# Bus_Isolator.net
KiCad netlist of a schematic drawn in EAGLE
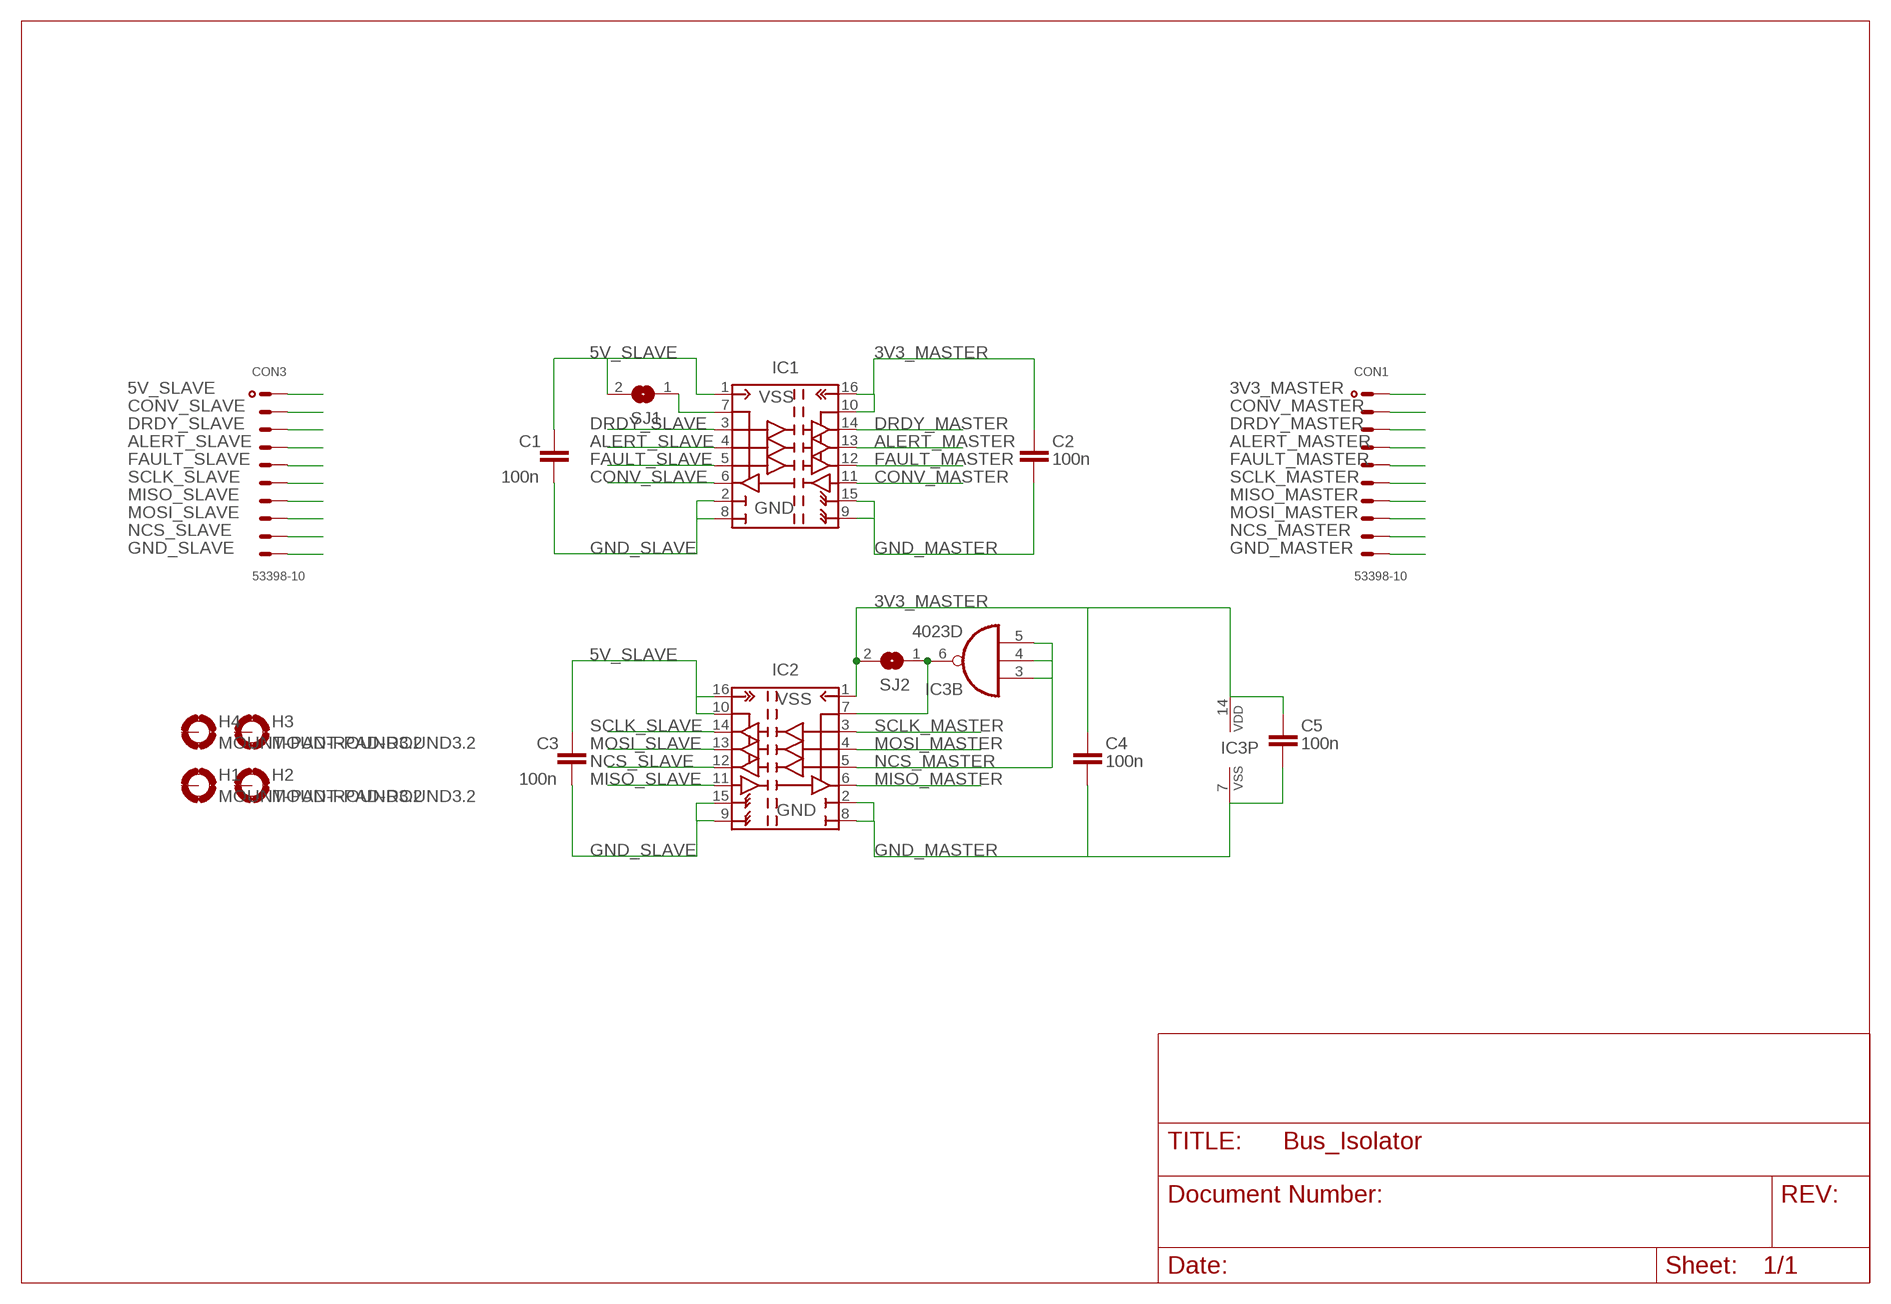
[diagram p0: schematic, sheet 1]

(export (version "E")
  (design (tool "Eeschema 10.0.6"))
  (components
    (comp (ref "C1")
      (value "100n")
      (footprint "eagle-import:C0805")
      (libsource (lib "eagle-import") (part "CSTD"))
    )
    (comp (ref "C2")
      (value "100n")
      (footprint "eagle-import:C0805")
      (libsource (lib "eagle-import") (part "CSTD"))
    )
    (comp (ref "C3")
      (value "100n")
      (footprint "eagle-import:C0805")
      (libsource (lib "eagle-import") (part "CSTD"))
    )
    (comp (ref "C4")
      (value "100n")
      (footprint "eagle-import:C0805")
      (libsource (lib "eagle-import") (part "CSTD"))
    )
    (comp (ref "C5")
      (value "100n")
      (footprint "eagle-import:C0805")
      (libsource (lib "eagle-import") (part "CSTD"))
    )
    (comp (ref "CON1")
      (value "53398-10")
      (footprint "eagle-import:53398-10")
      (libsource (lib "eagle-import") (part "53?-10398"))
    )
    (comp (ref "CON3")
      (value "53398-10")
      (footprint "eagle-import:53398-10")
      (libsource (lib "eagle-import") (part "53?-10398"))
    )
    (comp (ref "H1")
      (value "MOUNT-PAD-ROUND3.2")
      (footprint "eagle-import:3,2-PAD")
      (libsource (lib "eagle-import") (part "MOUNT-PAD-ROUND3.2"))
    )
    (comp (ref "H2")
      (value "MOUNT-PAD-ROUND3.2")
      (footprint "eagle-import:3,2-PAD")
      (libsource (lib "eagle-import") (part "MOUNT-PAD-ROUND3.2"))
    )
    (comp (ref "H3")
      (value "MOUNT-PAD-ROUND3.2")
      (footprint "eagle-import:3,2-PAD")
      (libsource (lib "eagle-import") (part "MOUNT-PAD-ROUND3.2"))
    )
    (comp (ref "H4")
      (value "MOUNT-PAD-ROUND3.2")
      (footprint "eagle-import:3,2-PAD")
      (libsource (lib "eagle-import") (part "MOUNT-PAD-ROUND3.2"))
    )
    (comp (ref "IC1")
      (value "ISO7241")
      (footprint "eagle-import:R-PDSO-G16")
      (libsource (lib "eagle-import") (part "ISO7241"))
    )
    (comp (ref "IC2")
      (value "ISO7241")
      (footprint "eagle-import:R-PDSO-G16")
      (libsource (lib "eagle-import") (part "ISO7241"))
    )
    (comp (ref "IC3")
      (value "4023D")
      (footprint "eagle-import:SO14")
      (libsource (lib "eagle-import") (part "4023D"))
    )
    (comp (ref "SJ1") (value "SJ") (footprint "eagle-import:SJ") (libsource (lib "eagle-import") (part "SJ")))
    (comp (ref "SJ2") (value "SJ") (footprint "eagle-import:SJ") (libsource (lib "eagle-import") (part "SJ")))
  )
  (nets
    (net (code "1") (name "/3V3_MASTER") (class "Default")
      (node (ref "C2") (pin "2") (pinfunction "2_2") (pintype "passive"))
      (node (ref "C4") (pin "2") (pinfunction "2_2") (pintype "passive"))
      (node (ref "C5") (pin "2") (pinfunction "2_2") (pintype "passive"))
      (node (ref "CON1") (pin "1") (pinfunction "1_1") (pintype "passive"))
      (node (ref "IC1") (pin "10") (pinfunction "EN2_10") (pintype "bidirectional"))
      (node (ref "IC1") (pin "16") (pinfunction "VCC2_16") (pintype "bidirectional"))
      (node (ref "IC2") (pin "1") (pinfunction "VCC1_1") (pintype "bidirectional"))
      (node (ref "IC3") (pin "14") (pinfunction "VDD_14") (pintype "power_in"))
      (node (ref "SJ2") (pin "2") (pinfunction "2_2") (pintype "passive"))
    )
    (net (code "2") (name "/5V_SLAVE") (class "Default")
      (node (ref "C1") (pin "2") (pinfunction "2_2") (pintype "passive"))
      (node (ref "C3") (pin "2") (pinfunction "2_2") (pintype "passive"))
      (node (ref "CON3") (pin "1") (pinfunction "1_1") (pintype "passive"))
      (node (ref "IC1") (pin "1") (pinfunction "VCC1_1") (pintype "bidirectional"))
      (node (ref "IC2") (pin "10") (pinfunction "EN2_10") (pintype "bidirectional"))
      (node (ref "IC2") (pin "16") (pinfunction "VCC2_16") (pintype "bidirectional"))
      (node (ref "SJ1") (pin "2") (pinfunction "2_2") (pintype "passive"))
    )
    (net (code "3") (name "/ALERT_MASTER") (class "Default")
      (node (ref "CON1") (pin "4") (pinfunction "4_4") (pintype "passive"))
      (node (ref "IC1") (pin "13") (pinfunction "OUT_B_13") (pintype "bidirectional"))
    )
    (net (code "4") (name "/ALERT_SLAVE") (class "Default")
      (node (ref "CON3") (pin "4") (pinfunction "4_4") (pintype "passive"))
      (node (ref "IC1") (pin "4") (pinfunction "IN_B_4") (pintype "bidirectional"))
    )
    (net (code "5") (name "/CONV_MASTER") (class "Default")
      (node (ref "CON1") (pin "2") (pinfunction "2_2") (pintype "passive"))
      (node (ref "IC1") (pin "11") (pinfunction "IN_D_11") (pintype "bidirectional"))
    )
    (net (code "6") (name "/CONV_SLAVE") (class "Default")
      (node (ref "CON3") (pin "2") (pinfunction "2_2") (pintype "passive"))
      (node (ref "IC1") (pin "6") (pinfunction "OUT_D_6") (pintype "bidirectional"))
    )
    (net (code "7") (name "/DRDY_MASTER") (class "Default")
      (node (ref "CON1") (pin "3") (pinfunction "3_3") (pintype "passive"))
      (node (ref "IC1") (pin "14") (pinfunction "OUT_A_14") (pintype "bidirectional"))
    )
    (net (code "8") (name "/DRDY_SLAVE") (class "Default")
      (node (ref "CON3") (pin "3") (pinfunction "3_3") (pintype "passive"))
      (node (ref "IC1") (pin "3") (pinfunction "IN_A_3") (pintype "bidirectional"))
    )
    (net (code "9") (name "/FAULT_MASTER") (class "Default")
      (node (ref "CON1") (pin "5") (pinfunction "5_5") (pintype "passive"))
      (node (ref "IC1") (pin "12") (pinfunction "OUT_C_12") (pintype "bidirectional"))
    )
    (net (code "10") (name "/FAULT_SLAVE") (class "Default")
      (node (ref "CON3") (pin "5") (pinfunction "5_5") (pintype "passive"))
      (node (ref "IC1") (pin "5") (pinfunction "IN_C_5") (pintype "bidirectional"))
    )
    (net (code "11") (name "/GND_MASTER") (class "Default")
      (node (ref "C2") (pin "1") (pinfunction "1_1") (pintype "passive"))
      (node (ref "C4") (pin "1") (pinfunction "1_1") (pintype "passive"))
      (node (ref "C5") (pin "1") (pinfunction "1_1") (pintype "passive"))
      (node (ref "CON1") (pin "10") (pinfunction "10_10") (pintype "passive"))
      (node (ref "IC1") (pin "15") (pinfunction "GND21_15") (pintype "bidirectional"))
      (node (ref "IC1") (pin "9") (pinfunction "GND22_9") (pintype "bidirectional"))
      (node (ref "IC2") (pin "2") (pinfunction "GND11_2") (pintype "bidirectional"))
      (node (ref "IC2") (pin "8") (pinfunction "GND12_8") (pintype "bidirectional"))
      (node (ref "IC3") (pin "7") (pinfunction "VSS_7") (pintype "power_in"))
    )
    (net (code "12") (name "/GND_SLAVE") (class "Default")
      (node (ref "C1") (pin "1") (pinfunction "1_1") (pintype "passive"))
      (node (ref "C3") (pin "1") (pinfunction "1_1") (pintype "passive"))
      (node (ref "CON3") (pin "10") (pinfunction "10_10") (pintype "passive"))
      (node (ref "IC1") (pin "2") (pinfunction "GND11_2") (pintype "bidirectional"))
      (node (ref "IC1") (pin "8") (pinfunction "GND12_8") (pintype "bidirectional"))
      (node (ref "IC2") (pin "15") (pinfunction "GND21_15") (pintype "bidirectional"))
      (node (ref "IC2") (pin "9") (pinfunction "GND22_9") (pintype "bidirectional"))
    )
    (net (code "13") (name "/MISO_MASTER") (class "Default")
      (node (ref "CON1") (pin "7") (pinfunction "7_7") (pintype "passive"))
      (node (ref "IC2") (pin "6") (pinfunction "OUT_D_6") (pintype "bidirectional"))
    )
    (net (code "14") (name "/MISO_SLAVE") (class "Default")
      (node (ref "CON3") (pin "7") (pinfunction "7_7") (pintype "passive"))
      (node (ref "IC2") (pin "11") (pinfunction "IN_D_11") (pintype "bidirectional"))
    )
    (net (code "15") (name "/MOSI_MASTER") (class "Default")
      (node (ref "CON1") (pin "8") (pinfunction "8_8") (pintype "passive"))
      (node (ref "IC2") (pin "4") (pinfunction "IN_B_4") (pintype "bidirectional"))
    )
    (net (code "16") (name "/MOSI_SLAVE") (class "Default")
      (node (ref "CON3") (pin "8") (pinfunction "8_8") (pintype "passive"))
      (node (ref "IC2") (pin "13") (pinfunction "OUT_B_13") (pintype "bidirectional"))
    )
    (net (code "17") (name "/NCS_MASTER") (class "Default")
      (node (ref "CON1") (pin "9") (pinfunction "9_9") (pintype "passive"))
      (node (ref "IC2") (pin "5") (pinfunction "IN_C_5") (pintype "bidirectional"))
      (node (ref "IC3") (pin "3") (pinfunction "I0_3") (pintype "input"))
      (node (ref "IC3") (pin "4") (pinfunction "I1_4") (pintype "input"))
      (node (ref "IC3") (pin "5") (pinfunction "I2_5") (pintype "input"))
    )
    (net (code "18") (name "/NCS_SLAVE") (class "Default")
      (node (ref "CON3") (pin "9") (pinfunction "9_9") (pintype "passive"))
      (node (ref "IC2") (pin "12") (pinfunction "OUT_C_12") (pintype "bidirectional"))
    )
    (net (code "19") (name "/SCLK_MASTER") (class "Default")
      (node (ref "CON1") (pin "6") (pinfunction "6_6") (pintype "passive"))
      (node (ref "IC2") (pin "3") (pinfunction "IN_A_3") (pintype "bidirectional"))
    )
    (net (code "20") (name "/SCLK_SLAVE") (class "Default")
      (node (ref "CON3") (pin "6") (pinfunction "6_6") (pintype "passive"))
      (node (ref "IC2") (pin "14") (pinfunction "OUT_A_14") (pintype "bidirectional"))
    )
    (net (code "21") (name "Net-(IC1-EN1)") (class "Default")
      (node (ref "IC1") (pin "7") (pinfunction "EN1_7") (pintype "bidirectional"))
      (node (ref "SJ1") (pin "1") (pinfunction "1_1") (pintype "passive"))
    )
    (net (code "22") (name "Net-(IC2-EN1)") (class "Default")
      (node (ref "IC2") (pin "7") (pinfunction "EN1_7") (pintype "bidirectional"))
      (node (ref "IC3") (pin "6") (pinfunction "O_6") (pintype "output"))
      (node (ref "SJ2") (pin "1") (pinfunction "1_1") (pintype "passive"))
    )
    (net (code "23") (name "unconnected-(H1-MOUNT-PadB3,2)") (class "Default")
      (node (ref "H1") (pin "B3,2") (pinfunction "MOUNT_B3,2") (pintype "passive"))
    )
    (net (code "24") (name "unconnected-(H2-MOUNT-PadB3,2)") (class "Default")
      (node (ref "H2") (pin "B3,2") (pinfunction "MOUNT_B3,2") (pintype "passive"))
    )
    (net (code "25") (name "unconnected-(H3-MOUNT-PadB3,2)") (class "Default")
      (node (ref "H3") (pin "B3,2") (pinfunction "MOUNT_B3,2") (pintype "passive"))
    )
    (net (code "26") (name "unconnected-(H4-MOUNT-PadB3,2)") (class "Default")
      (node (ref "H4") (pin "B3,2") (pinfunction "MOUNT_B3,2") (pintype "passive"))
    )
  )
)
